# PhaetonArduinoBrd.net
KiCad netlist of a schematic drawn in EAGLE
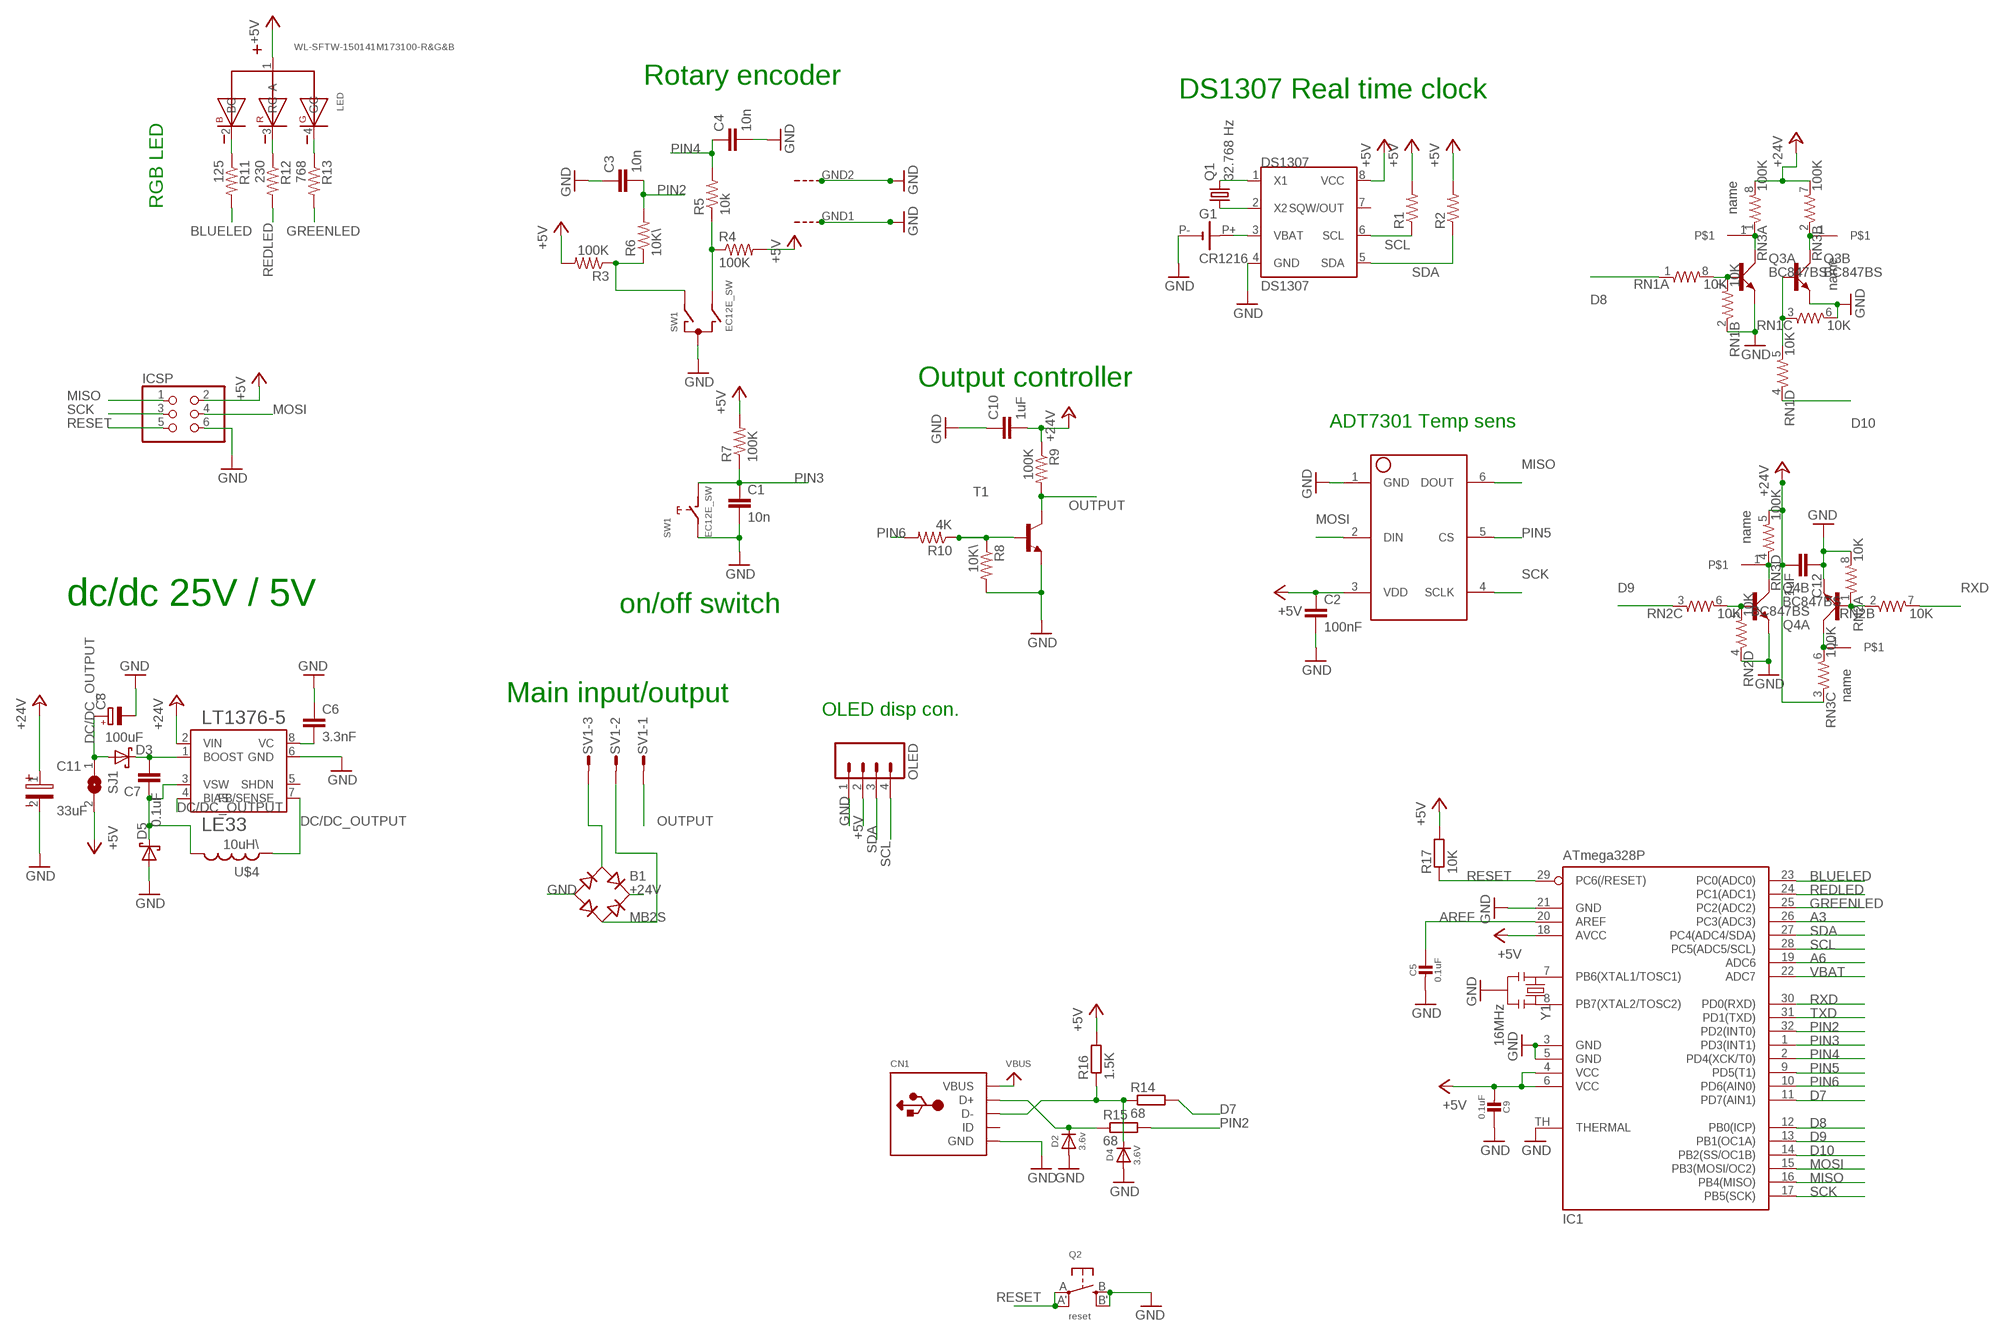
[diagram p0: schematic, sheet 1]

(export (version "E")
  (design (tool "Eeschema 10.0.6"))
  (components
    (comp (ref "ADT")
      (value "ADT7301")
      (footprint "eagle-import:SOT23-6")
      (libsource (lib "eagle-import") (part "ADT7301"))
    )
    (comp (ref "B1")
      (value "MB2S")
      (footprint "eagle-import:SOIC-4")
      (libsource (lib "eagle-import") (part "MBS2"))
    )
    (comp (ref "C1")
      (value "10n")
      (footprint "eagle-import:C0504")
      (libsource (lib "eagle-import") (part "C-EUC0504"))
    )
    (comp (ref "C2")
      (value "100nF")
      (footprint "eagle-import:C0504")
      (libsource (lib "eagle-import") (part "C-EUC0504"))
    )
    (comp (ref "C3")
      (value "10n")
      (footprint "eagle-import:C0504")
      (libsource (lib "eagle-import") (part "C-EUC0504"))
    )
    (comp (ref "C4")
      (value "10n")
      (footprint "eagle-import:C0504")
      (libsource (lib "eagle-import") (part "C-EUC0504"))
    )
    (comp (ref "C5")
      (value "0.1uF")
      (footprint "eagle-import:_0805MP")
      (libsource (lib "eagle-import") (part "CAP_CERAMIC_0805MP"))
    )
    (comp (ref "C6")
      (value "3.3nF")
      (footprint "eagle-import:C0504")
      (libsource (lib "eagle-import") (part "C-EUC0504"))
    )
    (comp (ref "C7")
      (value "0.1uF")
      (footprint "eagle-import:C0504")
      (libsource (lib "eagle-import") (part "C-EUC0504"))
    )
    (comp (ref "C8")
      (value "100uF")
      (footprint "eagle-import:CT7343")
      (libsource (lib "eagle-import") (part "CPOL-EUCT7343"))
    )
    (comp (ref "C9")
      (value "0.1uF")
      (footprint "eagle-import:_0805MP")
      (libsource (lib "eagle-import") (part "CAP_CERAMIC_0805MP"))
    )
    (comp (ref "C10")
      (value "1uF")
      (footprint "eagle-import:C0402")
      (libsource (lib "eagle-import") (part "resistor_C-EUC0402"))
    )
    (comp (ref "C11")
      (value "33uF")
      (footprint "eagle-import:3X1.6X1.4(BXCXA)")
      (libsource (lib "eagle-import") (part "WCAP-ASLI_5X5.5(DXL)"))
    )
    (comp (ref "C12")
      (value "1uF")
      (footprint "eagle-import:C0402")
      (libsource (lib "eagle-import") (part "resistor_C-EUC0402"))
    )
    (comp (ref "CN1")
      (value "USBMINIB")
      (footprint "eagle-import:USB-MINIB")
      (libsource (lib "eagle-import") (part "USBMINIB"))
    )
    (comp (ref "D2")
      (value "3.6v")
      (footprint "eagle-import:SOD-323")
      (libsource (lib "eagle-import") (part "DIODESOD-323"))
    )
    (comp (ref "D3")
      (value "SCHOTTKY")
      (footprint "eagle-import:DO214")
      (libsource (lib "eagle-import") (part "SCHOTTKY"))
    )
    (comp (ref "D4")
      (value "3.6V")
      (footprint "eagle-import:SOD-323")
      (libsource (lib "eagle-import") (part "DIODESOD-323"))
    )
    (comp (ref "D5")
      (value "SCHOTTKY")
      (footprint "eagle-import:DO214")
      (libsource (lib "eagle-import") (part "SCHOTTKY"))
    )
    (comp (ref "DS1307")
      (value "DS1307")
      (footprint "eagle-import:SOIC-8")
      (libsource (lib "eagle-import") (part "DS1307"))
    )
    (comp (ref "G1")
      (value "CR1216")
      (footprint "eagle-import:SMTU1225-LF")
      (libsource (lib "eagle-import") (part "CR1216"))
    )
    (comp (ref "IC1")
      (value "ATmega328P")
      (footprint "eagle-import:MLF32-TH")
      (fields (field (name "MPN") "ATMEGA88PA-MU"))
      (libsource (lib "eagle-import") (part "MEGA8-MI"))
    )
    (comp (ref "ICSP")
      (value "PINHD-2X3")
      (footprint "eagle-import:2X03")
      (libsource (lib "eagle-import") (part "PINHD-2X3"))
    )
    (comp (ref "LED")
      (value "WL-SFTW-150141M173100-R&G&B")
      (footprint "eagle-import:3528-COMMON-ANODE")
      (libsource (lib "eagle-import") (part "WL-SFTW-150141M173100-R&G&B"))
    )
    (comp (ref "LT1376-5")
      (value "LE33")
      (footprint "eagle-import:SO08")
      (libsource (lib "eagle-import") (part "LE33"))
    )
    (comp (ref "OLED")
      (value "M04")
      (footprint "eagle-import:04P")
      (libsource (lib "eagle-import") (part "M04"))
    )
    (comp (ref "OUTPUT2")
      (value "MINICONECTOR")
      (footprint "eagle-import:SMD")
      (libsource (lib "eagle-import") (part "MINICONECTOR"))
    )
    (comp (ref "Q1")
      (value "32.768 Hz")
      (footprint "eagle-import:TC26V")
      (libsource (lib "eagle-import") (part "CRYSTALTC26V"))
    )
    (comp (ref "Q2")
      (value "reset")
      (footprint "eagle-import:BTN_KMR2_4.6X2.8")
      (libsource (lib "eagle-import") (part "SWITCH_TACT_SMT4.6X2.8"))
    )
    (comp (ref "Q3")
      (value "BC847BS")
      (footprint "eagle-import:SOT363_PHILIPS")
      (libsource (lib "eagle-import") (part "BC847BS"))
    )
    (comp (ref "Q4")
      (value "BC847BS")
      (footprint "eagle-import:SOT363_PHILIPS")
      (libsource (lib "eagle-import") (part "BC847BS"))
    )
    (comp (ref "R1")
      (value "RESISTOR")
      (footprint "eagle-import:0805")
      (libsource (lib "eagle-import") (part "RESISTOR"))
    )
    (comp (ref "R2")
      (value "RESISTOR")
      (footprint "eagle-import:0805")
      (libsource (lib "eagle-import") (part "RESISTOR"))
    )
    (comp (ref "R3")
      (value "100K")
      (footprint "eagle-import:0805")
      (libsource (lib "eagle-import") (part "RESISTOR"))
    )
    (comp (ref "R4")
      (value "100K")
      (footprint "eagle-import:0805")
      (libsource (lib "eagle-import") (part "RESISTOR"))
    )
    (comp (ref "R5")
      (value "10k")
      (footprint "eagle-import:0805")
      (libsource (lib "eagle-import") (part "RESISTOR"))
    )
    (comp (ref "R6")
      (value "10K\\")
      (footprint "eagle-import:0805")
      (libsource (lib "eagle-import") (part "RESISTOR"))
    )
    (comp (ref "R7")
      (value "100K")
      (footprint "eagle-import:0805")
      (libsource (lib "eagle-import") (part "RESISTOR"))
    )
    (comp (ref "R8")
      (value "10K\\")
      (footprint "eagle-import:0805")
      (libsource (lib "eagle-import") (part "RESISTOR"))
    )
    (comp (ref "R9")
      (value "100K")
      (footprint "eagle-import:0805")
      (libsource (lib "eagle-import") (part "RESISTOR"))
    )
    (comp (ref "R10")
      (value "4K")
      (footprint "eagle-import:0805")
      (libsource (lib "eagle-import") (part "RESISTOR"))
    )
    (comp (ref "R11")
      (value "125")
      (footprint "eagle-import:0805")
      (libsource (lib "eagle-import") (part "RESISTOR"))
    )
    (comp (ref "R12")
      (value "230")
      (footprint "eagle-import:0805")
      (libsource (lib "eagle-import") (part "RESISTOR"))
    )
    (comp (ref "R13")
      (value "768")
      (footprint "eagle-import:0805")
      (libsource (lib "eagle-import") (part "RESISTOR"))
    )
    (comp (ref "R14")
      (value "68")
      (footprint "eagle-import:R0603")
      (libsource (lib "eagle-import") (part "R-EU_R0603"))
    )
    (comp (ref "R15")
      (value "68")
      (footprint "eagle-import:R0603")
      (libsource (lib "eagle-import") (part "R-EU_R0603"))
    )
    (comp (ref "R16")
      (value "1.5K")
      (footprint "eagle-import:R0603")
      (libsource (lib "eagle-import") (part "R-EU_R0603"))
    )
    (comp (ref "R17")
      (value "10K")
      (footprint "eagle-import:R0603")
      (libsource (lib "eagle-import") (part "R-EU_R0603"))
    )
    (comp (ref "RN1")
      (value "10K")
      (footprint "eagle-import:741-8")
      (libsource (lib "eagle-import") (part "741-8_S"))
    )
    (comp (ref "RN2")
      (value "10K")
      (footprint "eagle-import:741-8")
      (libsource (lib "eagle-import") (part "741-8_S"))
    )
    (comp (ref "RN3")
      (value "100K")
      (footprint "eagle-import:741-8")
      (libsource (lib "eagle-import") (part "741-8_S"))
    )
    (comp (ref "SJ1") (value "SJ") (footprint "eagle-import:SJ") (libsource (lib "eagle-import") (part "SJ")))
    (comp (ref "SV1")
      (value "MT6-3")
      (footprint "eagle-import:MT6-3")
      (libsource (lib "eagle-import") (part "MT6-3"))
    )
    (comp (ref "SW1")
      (value "EC12E_SW")
      (footprint "eagle-import:ALPS_EC12E_SW")
      (fields (field (name "MPN") "EC12E2424407"))
      (libsource (lib "eagle-import") (part "EC12E_SW"))
    )
    (comp (ref "T1")
      (value "BC818-16-NPN-SOT23-BEC")
      (footprint "eagle-import:SOT23-BEC")
      (libsource (lib "eagle-import") (part "-NPN-SOT23-BECBC818-16"))
    )
    (comp (ref "U$3")
      (value "MINICONECTOR")
      (footprint "eagle-import:SMD")
      (libsource (lib "eagle-import") (part "MINICONECTOR"))
    )
    (comp (ref "U$4")
      (value "10uH\\")
      (footprint "eagle-import:103MRB")
      (libsource (lib "eagle-import") (part "LPS3314-103MRB"))
    )
    (comp (ref "U$5")
      (value "MINICONECTOR")
      (footprint "eagle-import:SMD")
      (libsource (lib "eagle-import") (part "MINICONECTOR"))
    )
    (comp (ref "U$6")
      (value "MINICONECTOR")
      (footprint "eagle-import:SMD")
      (libsource (lib "eagle-import") (part "MINICONECTOR"))
    )
    (comp (ref "Y1")
      (value "16MHz")
      (footprint "eagle-import:RESONATOR-SMD")
      (libsource (lib "eagle-import") (part "RESONATORSMD"))
    )
  )
  (nets
    (net (code "1") (name "+5V") (class "Default")
      (node (ref "ADT") (pin "3") (pinfunction "VDD_3") (pintype "bidirectional"))
      (node (ref "C2") (pin "1") (pinfunction "1_1") (pintype "passive"))
      (node (ref "C9") (pin "2") (pinfunction "2_2") (pintype "passive"))
      (node (ref "DS1307") (pin "8") (pinfunction "VCC_8") (pintype "power_in"))
      (node (ref "IC1") (pin "18") (pinfunction "AVCC_18") (pintype "power_in"))
      (node (ref "IC1") (pin "4") (pinfunction "VCC_4") (pintype "power_in"))
      (node (ref "IC1") (pin "6") (pinfunction "VCC_6") (pintype "power_in"))
      (node (ref "ICSP") (pin "2") (pinfunction "2_2") (pintype "passive"))
      (node (ref "LED") (pin "1") (pinfunction "A_1") (pintype "bidirectional"))
      (node (ref "OLED") (pin "2") (pinfunction "2_2") (pintype "passive"))
      (node (ref "R1") (pin "2") (pinfunction "2_2") (pintype "passive"))
      (node (ref "R16") (pin "2") (pinfunction "2_2") (pintype "passive"))
      (node (ref "R17") (pin "2") (pinfunction "2_2") (pintype "passive"))
      (node (ref "R2") (pin "2") (pinfunction "2_2") (pintype "passive"))
      (node (ref "R3") (pin "2") (pinfunction "2_2") (pintype "passive"))
      (node (ref "R4") (pin "2") (pinfunction "2_2") (pintype "passive"))
      (node (ref "R7") (pin "2") (pinfunction "2_2") (pintype "passive"))
      (node (ref "SJ1") (pin "2") (pinfunction "2_2") (pintype "passive"))
    )
    (net (code "2") (name "+24V") (class "Default")
      (node (ref "B1") (pin "+") (pinfunction "+_+") (pintype "passive"))
      (node (ref "C10") (pin "2") (pinfunction "2_2") (pintype "passive"))
      (node (ref "C11") (pin "1") (pinfunction "1_1") (pintype "bidirectional"))
      (node (ref "C12") (pin "2") (pinfunction "2_2") (pintype "passive"))
      (node (ref "LT1376-5") (pin "2") (pinfunction "VIN_2") (pintype "input"))
      (node (ref "R9") (pin "1") (pinfunction "1_1") (pintype "passive"))
      (node (ref "RN3") (pin "3") (pinfunction "1_3") (pintype "passive"))
      (node (ref "RN3") (pin "5") (pinfunction "2_5") (pintype "passive"))
      (node (ref "RN3") (pin "7") (pinfunction "2_7") (pintype "passive"))
      (node (ref "RN3") (pin "8") (pinfunction "2_8") (pintype "passive"))
    )
    (net (code "3") (name "/A3") (class "Default")
      (node (ref "IC1") (pin "26") (pinfunction "PC3(ADC3)_26") (pintype "bidirectional"))
    )
    (net (code "4") (name "/A6") (class "Default")
      (node (ref "IC1") (pin "19") (pinfunction "ADC6_19") (pintype "bidirectional"))
    )
    (net (code "5") (name "/AREF") (class "Default")
      (node (ref "C5") (pin "1") (pinfunction "1_1") (pintype "passive"))
      (node (ref "IC1") (pin "20") (pinfunction "AREF_20") (pintype "passive"))
    )
    (net (code "6") (name "/BLUELED") (class "Default")
      (node (ref "IC1") (pin "23") (pinfunction "PC0(ADC0)_23") (pintype "bidirectional"))
      (node (ref "R11") (pin "2") (pinfunction "2_2") (pintype "passive"))
    )
    (net (code "7") (name "/D7") (class "Default")
      (node (ref "IC1") (pin "11") (pinfunction "PD7(AIN1)_11") (pintype "bidirectional"))
      (node (ref "R14") (pin "2") (pinfunction "2_2") (pintype "passive"))
    )
    (net (code "8") (name "/D8") (class "Default")
      (node (ref "IC1") (pin "12") (pinfunction "PB0(ICP)_12") (pintype "bidirectional"))
      (node (ref "RN1") (pin "1") (pinfunction "1_1") (pintype "passive"))
    )
    (net (code "9") (name "/D9") (class "Default")
      (node (ref "IC1") (pin "13") (pinfunction "PB1(OC1A)_13") (pintype "bidirectional"))
      (node (ref "RN2") (pin "3") (pinfunction "1_3") (pintype "passive"))
    )
    (net (code "10") (name "/D10") (class "Default")
      (node (ref "IC1") (pin "14") (pinfunction "PB2(SS/OC1B)_14") (pintype "bidirectional"))
      (node (ref "RN1") (pin "4") (pinfunction "1_4") (pintype "passive"))
    )
    (net (code "11") (name "/DC{slash}DC_OUTPUT") (class "Default")
      (node (ref "C8") (pin "+") (pinfunction "+_+") (pintype "passive"))
      (node (ref "D3") (pin "A") (pinfunction "A_A") (pintype "passive"))
      (node (ref "LT1376-5") (pin "4") (pinfunction "BIAS_4") (pintype "power_in"))
      (node (ref "LT1376-5") (pin "7") (pinfunction "FB/SENSE_7") (pintype "bidirectional"))
      (node (ref "SJ1") (pin "1") (pinfunction "1_1") (pintype "passive"))
      (node (ref "U$4") (pin "2") (pinfunction "P$2_2") (pintype "passive"))
    )
    (net (code "12") (name "/GREENLED") (class "Default")
      (node (ref "IC1") (pin "25") (pinfunction "PC2(ADC2)_25") (pintype "bidirectional"))
      (node (ref "R13") (pin "2") (pinfunction "2_2") (pintype "passive"))
    )
    (net (code "13") (name "/MISO") (class "Default")
      (node (ref "ADT") (pin "6") (pinfunction "DOUT_6") (pintype "bidirectional"))
      (node (ref "IC1") (pin "16") (pinfunction "PB4(MISO)_16") (pintype "bidirectional"))
      (node (ref "ICSP") (pin "1") (pinfunction "1_1") (pintype "passive"))
    )
    (net (code "14") (name "/MOSI") (class "Default")
      (node (ref "ADT") (pin "2") (pinfunction "DIN_2") (pintype "bidirectional"))
      (node (ref "IC1") (pin "15") (pinfunction "PB3(MOSI/OC2)_15") (pintype "bidirectional"))
      (node (ref "ICSP") (pin "4") (pinfunction "4_4") (pintype "passive"))
    )
    (net (code "15") (name "/OUTPUT") (class "Default")
      (node (ref "R9") (pin "2") (pinfunction "2_2") (pintype "passive"))
      (node (ref "SV1") (pin "1") (pinfunction "S_1") (pintype "passive"))
      (node (ref "T1") (pin "C") (pinfunction "C_C") (pintype "passive"))
    )
    (net (code "16") (name "/PIN2") (class "Default")
      (node (ref "C3") (pin "2") (pinfunction "2_2") (pintype "passive"))
      (node (ref "IC1") (pin "32") (pinfunction "PD2(INT0)_32") (pintype "bidirectional"))
      (node (ref "R15") (pin "2") (pinfunction "2_2") (pintype "passive"))
      (node (ref "R6") (pin "2") (pinfunction "2_2") (pintype "passive"))
    )
    (net (code "17") (name "/PIN3") (class "Default")
      (node (ref "C1") (pin "1") (pinfunction "1_1") (pintype "passive"))
      (node (ref "IC1") (pin "1") (pinfunction "PD3(INT1)_1") (pintype "bidirectional"))
      (node (ref "R7") (pin "1") (pinfunction "1_1") (pintype "passive"))
      (node (ref "SW1") (pin "D") (pinfunction "1_D") (pintype "passive"))
    )
    (net (code "18") (name "/PIN4") (class "Default")
      (node (ref "C4") (pin "1") (pinfunction "1_1") (pintype "passive"))
      (node (ref "IC1") (pin "2") (pinfunction "PD4(XCK/T0)_2") (pintype "bidirectional"))
      (node (ref "R5") (pin "2") (pinfunction "2_2") (pintype "passive"))
    )
    (net (code "19") (name "/PIN5") (class "Default")
      (node (ref "ADT") (pin "5") (pinfunction "CS_5") (pintype "bidirectional"))
      (node (ref "IC1") (pin "9") (pinfunction "PD5(T1)_9") (pintype "bidirectional"))
    )
    (net (code "20") (name "/PIN6") (class "Default")
      (node (ref "IC1") (pin "10") (pinfunction "PD6(AIN0)_10") (pintype "bidirectional"))
      (node (ref "R10") (pin "2") (pinfunction "2_2") (pintype "passive"))
    )
    (net (code "21") (name "/REDLED") (class "Default")
      (node (ref "IC1") (pin "24") (pinfunction "PC1(ADC1)_24") (pintype "bidirectional"))
      (node (ref "R12") (pin "2") (pinfunction "2_2") (pintype "passive"))
    )
    (net (code "22") (name "/RESET") (class "Default")
      (node (ref "IC1") (pin "29") (pinfunction "PC6(/RESET)_29") (pintype "bidirectional"))
      (node (ref "ICSP") (pin "5") (pinfunction "5_5") (pintype "passive"))
      (node (ref "Q2") (pin "A") (pinfunction "P_A") (pintype "passive"))
      (node (ref "Q2") (pin "A'") (pinfunction "P1_A'") (pintype "passive"))
      (node (ref "R17") (pin "1") (pinfunction "1_1") (pintype "passive"))
    )
    (net (code "23") (name "/RXD") (class "Default")
      (node (ref "IC1") (pin "30") (pinfunction "PD0(RXD)_30") (pintype "bidirectional"))
      (node (ref "RN2") (pin "7") (pinfunction "2_7") (pintype "passive"))
    )
    (net (code "24") (name "/SCK") (class "Default")
      (node (ref "ADT") (pin "4") (pinfunction "SCLK_4") (pintype "bidirectional"))
      (node (ref "IC1") (pin "17") (pinfunction "PB5(SCK)_17") (pintype "bidirectional"))
      (node (ref "ICSP") (pin "3") (pinfunction "3_3") (pintype "passive"))
    )
    (net (code "25") (name "/SCL") (class "Default")
      (node (ref "DS1307") (pin "6") (pinfunction "SCL_6") (pintype "input"))
      (node (ref "IC1") (pin "28") (pinfunction "PC5(ADC5/SCL)_28") (pintype "bidirectional"))
      (node (ref "OLED") (pin "4") (pinfunction "4_4") (pintype "passive"))
      (node (ref "R1") (pin "1") (pinfunction "1_1") (pintype "passive"))
    )
    (net (code "26") (name "/SDA") (class "Default")
      (node (ref "DS1307") (pin "5") (pinfunction "SDA_5") (pintype "bidirectional"))
      (node (ref "IC1") (pin "27") (pinfunction "PC4(ADC4/SDA)_27") (pintype "bidirectional"))
      (node (ref "OLED") (pin "3") (pinfunction "3_3") (pintype "passive"))
      (node (ref "R2") (pin "1") (pinfunction "1_1") (pintype "passive"))
    )
    (net (code "27") (name "/SHDN") (class "Default")
      (node (ref "LT1376-5") (pin "5") (pinfunction "SHDN_5") (pintype "power_in"))
    )
    (net (code "28") (name "/TXD") (class "Default")
      (node (ref "IC1") (pin "31") (pinfunction "PD1(TXD)_31") (pintype "bidirectional"))
    )
    (net (code "29") (name "/VBAT") (class "Default")
      (node (ref "DS1307") (pin "3") (pinfunction "VBAT_3") (pintype "power_in"))
      (node (ref "G1") (pin "P+") (pinfunction "+_P+") (pintype "passive"))
      (node (ref "IC1") (pin "22") (pinfunction "ADC7_22") (pintype "bidirectional"))
    )
    (net (code "30") (name "GND") (class "Default")
      (node (ref "ADT") (pin "1") (pinfunction "GND_1") (pintype "bidirectional"))
      (node (ref "B1") (pin "-") (pinfunction "-_-") (pintype "passive"))
      (node (ref "C1") (pin "2") (pinfunction "2_2") (pintype "passive"))
      (node (ref "C10") (pin "1") (pinfunction "1_1") (pintype "passive"))
      (node (ref "C11") (pin "2") (pinfunction "2_2") (pintype "bidirectional"))
      (node (ref "C12") (pin "1") (pinfunction "1_1") (pintype "passive"))
      (node (ref "C2") (pin "2") (pinfunction "2_2") (pintype "passive"))
      (node (ref "C3") (pin "1") (pinfunction "1_1") (pintype "passive"))
      (node (ref "C4") (pin "2") (pinfunction "2_2") (pintype "passive"))
      (node (ref "C5") (pin "2") (pinfunction "2_2") (pintype "passive"))
      (node (ref "C6") (pin "1") (pinfunction "1_1") (pintype "passive"))
      (node (ref "C8") (pin "-") (pinfunction "-_-") (pintype "passive"))
      (node (ref "C9") (pin "1") (pinfunction "1_1") (pintype "passive"))
      (node (ref "CN1") (pin "GND") (pinfunction "GND_GND") (pintype "power_in"))
      (node (ref "D2") (pin "A") (pinfunction "A_A") (pintype "passive"))
      (node (ref "D4") (pin "A") (pinfunction "A_A") (pintype "passive"))
      (node (ref "D5") (pin "A") (pinfunction "A_A") (pintype "passive"))
      (node (ref "DS1307") (pin "4") (pinfunction "GND_4") (pintype "power_in"))
      (node (ref "G1") (pin "P-") (pinfunction "-_P-") (pintype "passive"))
      (node (ref "IC1") (pin "21") (pinfunction "GND_21") (pintype "power_in"))
      (node (ref "IC1") (pin "3") (pinfunction "GND_3") (pintype "power_in"))
      (node (ref "IC1") (pin "5") (pinfunction "GND_5") (pintype "power_in"))
      (node (ref "IC1") (pin "TH") (pinfunction "THERMAL_TH") (pintype "passive"))
      (node (ref "ICSP") (pin "6") (pinfunction "6_6") (pintype "passive"))
      (node (ref "LT1376-5") (pin "6") (pinfunction "GND_6") (pintype "power_in"))
      (node (ref "OLED") (pin "1") (pinfunction "1_1") (pintype "passive"))
      (node (ref "Q2") (pin "B") (pinfunction "S_B") (pintype "passive"))
      (node (ref "Q2") (pin "B'") (pinfunction "S1_B'") (pintype "passive"))
      (node (ref "Q3") (pin "1") (pinfunction "E_1") (pintype "passive"))
      (node (ref "Q3") (pin "4") (pinfunction "E_4") (pintype "passive"))
      (node (ref "Q4") (pin "1") (pinfunction "E_1") (pintype "passive"))
      (node (ref "Q4") (pin "4") (pinfunction "E_4") (pintype "passive"))
      (node (ref "R8") (pin "2") (pinfunction "2_2") (pintype "passive"))
      (node (ref "RN1") (pin "2") (pinfunction "1_2") (pintype "passive"))
      (node (ref "RN1") (pin "6") (pinfunction "2_6") (pintype "passive"))
      (node (ref "RN2") (pin "4") (pinfunction "1_4") (pintype "passive"))
      (node (ref "RN2") (pin "8") (pinfunction "2_8") (pintype "passive"))
      (node (ref "SW1") (pin "C") (pinfunction "C_C") (pintype "passive"))
      (node (ref "SW1") (pin "E") (pinfunction "2_E") (pintype "passive"))
      (node (ref "SW1") (pin "GND1") (pinfunction "G_GND1") (pintype "passive"))
      (node (ref "SW1") (pin "GND2") (pinfunction "G_GND2") (pintype "passive"))
      (node (ref "T1") (pin "E") (pinfunction "E_E") (pintype "passive"))
      (node (ref "Y1") (pin "2") (pinfunction "2_2") (pintype "passive"))
    )
    (net (code "31") (name "Net-(B1-AC1)") (class "Default")
      (node (ref "B1") (pin "~1") (pinfunction "AC1_~1") (pintype "passive"))
      (node (ref "SV1") (pin "3") (pinfunction "S_3") (pintype "passive"))
    )
    (net (code "32") (name "Net-(B1-AC2)") (class "Default")
      (node (ref "B1") (pin "~2") (pinfunction "AC2_~2") (pintype "passive"))
      (node (ref "SV1") (pin "2") (pinfunction "S_2") (pintype "passive"))
    )
    (net (code "33") (name "Net-(CN1-PadD+)") (class "Default")
      (node (ref "CN1") (pin "D+") (pinfunction "D+_D+") (pintype "bidirectional"))
      (node (ref "D2") (pin "C") (pinfunction "C_C") (pintype "passive"))
      (node (ref "R15") (pin "1") (pinfunction "1_1") (pintype "passive"))
    )
    (net (code "34") (name "Net-(CN1-PadD-)") (class "Default")
      (node (ref "CN1") (pin "D-") (pinfunction "D-_D-") (pintype "bidirectional"))
      (node (ref "D4") (pin "C") (pinfunction "C_C") (pintype "passive"))
      (node (ref "R14") (pin "1") (pinfunction "1_1") (pintype "passive"))
      (node (ref "R16") (pin "1") (pinfunction "1_1") (pintype "passive"))
    )
    (net (code "35") (name "Net-(DS1307-X1)") (class "Default")
      (node (ref "DS1307") (pin "1") (pinfunction "X1_1") (pintype "input"))
      (node (ref "Q1") (pin "2") (pinfunction "2_2") (pintype "passive"))
    )
    (net (code "36") (name "Net-(DS1307-X2)") (class "Default")
      (node (ref "DS1307") (pin "2") (pinfunction "X2_2") (pintype "output"))
      (node (ref "Q1") (pin "1") (pinfunction "1_1") (pintype "passive"))
    )
    (net (code "37") (name "Net-(IC1-PB6(XTAL1{slash}TOSC1))") (class "Default")
      (node (ref "IC1") (pin "7") (pinfunction "PB6(XTAL1/TOSC1)_7") (pintype "bidirectional"))
      (node (ref "Y1") (pin "1") (pinfunction "1_1") (pintype "passive"))
    )
    (net (code "38") (name "Net-(IC1-PB7(XTAL2{slash}TOSC2))") (class "Default")
      (node (ref "IC1") (pin "8") (pinfunction "PB7(XTAL2/TOSC2)_8") (pintype "bidirectional"))
      (node (ref "Y1") (pin "3") (pinfunction "3_3") (pintype "passive"))
    )
    (net (code "39") (name "Net-(LED-BC)") (class "Default")
      (node (ref "LED") (pin "2") (pinfunction "BC_2") (pintype "bidirectional"))
      (node (ref "R11") (pin "1") (pinfunction "1_1") (pintype "passive"))
    )
    (net (code "40") (name "Net-(LED-GC)") (class "Default")
      (node (ref "LED") (pin "4") (pinfunction "GC_4") (pintype "bidirectional"))
      (node (ref "R13") (pin "1") (pinfunction "1_1") (pintype "passive"))
    )
    (net (code "41") (name "Net-(LED-RC)") (class "Default")
      (node (ref "LED") (pin "3") (pinfunction "RC_3") (pintype "bidirectional"))
      (node (ref "R12") (pin "1") (pinfunction "1_1") (pintype "passive"))
    )
    (net (code "42") (name "Net-(LT1376-5-BOOST)") (class "Default")
      (node (ref "C7") (pin "2") (pinfunction "2_2") (pintype "passive"))
      (node (ref "D3") (pin "C") (pinfunction "C_C") (pintype "passive"))
      (node (ref "LT1376-5") (pin "1") (pinfunction "BOOST_1") (pintype "input"))
    )
    (net (code "43") (name "Net-(LT1376-5-VC)") (class "Default")
      (node (ref "C6") (pin "2") (pinfunction "2_2") (pintype "passive"))
      (node (ref "LT1376-5") (pin "8") (pinfunction "VC_8") (pintype "output"))
    )
    (net (code "44") (name "Net-(LT1376-5-VSW)") (class "Default")
      (node (ref "C7") (pin "1") (pinfunction "1_1") (pintype "passive"))
      (node (ref "D5") (pin "C") (pinfunction "C_C") (pintype "passive"))
      (node (ref "LT1376-5") (pin "3") (pinfunction "VSW_3") (pintype "power_in"))
      (node (ref "U$4") (pin "1") (pinfunction "P$1_1") (pintype "passive"))
    )
    (net (code "45") (name "Net-(OUTPUT2-P$1)") (class "Default")
      (node (ref "OUTPUT2") (pin "1") (pinfunction "P$1_1") (pintype "bidirectional"))
      (node (ref "Q3") (pin "6") (pinfunction "C_6") (pintype "passive"))
      (node (ref "RN3") (pin "1") (pinfunction "1_1") (pintype "passive"))
    )
    (net (code "46") (name "Net-(Q3A-B)") (class "Default")
      (node (ref "Q3") (pin "2") (pinfunction "B_2") (pintype "passive"))
      (node (ref "RN1") (pin "7") (pinfunction "2_7") (pintype "passive"))
      (node (ref "RN1") (pin "8") (pinfunction "2_8") (pintype "passive"))
    )
    (net (code "47") (name "Net-(Q3B-B)") (class "Default")
      (node (ref "Q3") (pin "5") (pinfunction "B_5") (pintype "passive"))
      (node (ref "RN1") (pin "3") (pinfunction "1_3") (pintype "passive"))
      (node (ref "RN1") (pin "5") (pinfunction "2_5") (pintype "passive"))
    )
    (net (code "48") (name "Net-(Q3B-C)") (class "Default")
      (node (ref "Q3") (pin "3") (pinfunction "C_3") (pintype "passive"))
      (node (ref "RN3") (pin "2") (pinfunction "1_2") (pintype "passive"))
      (node (ref "U$3") (pin "1") (pinfunction "P$1_1") (pintype "bidirectional"))
    )
    (net (code "49") (name "Net-(Q4A-B)") (class "Default")
      (node (ref "Q4") (pin "2") (pinfunction "B_2") (pintype "passive"))
      (node (ref "RN2") (pin "1") (pinfunction "1_1") (pintype "passive"))
      (node (ref "RN2") (pin "2") (pinfunction "1_2") (pintype "passive"))
    )
    (net (code "50") (name "Net-(Q4A-C)") (class "Default")
      (node (ref "Q4") (pin "6") (pinfunction "C_6") (pintype "passive"))
      (node (ref "RN3") (pin "6") (pinfunction "2_6") (pintype "passive"))
      (node (ref "U$5") (pin "1") (pinfunction "P$1_1") (pintype "bidirectional"))
    )
    (net (code "51") (name "Net-(Q4B-B)") (class "Default")
      (node (ref "Q4") (pin "5") (pinfunction "B_5") (pintype "passive"))
      (node (ref "RN2") (pin "5") (pinfunction "2_5") (pintype "passive"))
      (node (ref "RN2") (pin "6") (pinfunction "2_6") (pintype "passive"))
    )
    (net (code "52") (name "Net-(Q4B-C)") (class "Default")
      (node (ref "Q4") (pin "3") (pinfunction "C_3") (pintype "passive"))
      (node (ref "RN3") (pin "4") (pinfunction "1_4") (pintype "passive"))
      (node (ref "U$6") (pin "1") (pinfunction "P$1_1") (pintype "bidirectional"))
    )
    (net (code "53") (name "Net-(R3-Pad1)") (class "Default")
      (node (ref "R3") (pin "1") (pinfunction "1_1") (pintype "passive"))
      (node (ref "R6") (pin "1") (pinfunction "1_1") (pintype "passive"))
      (node (ref "SW1") (pin "A") (pinfunction "A_A") (pintype "passive"))
    )
    (net (code "54") (name "Net-(R4-Pad1)") (class "Default")
      (node (ref "R4") (pin "1") (pinfunction "1_1") (pintype "passive"))
      (node (ref "R5") (pin "1") (pinfunction "1_1") (pintype "passive"))
      (node (ref "SW1") (pin "B") (pinfunction "B_B") (pintype "passive"))
    )
    (net (code "55") (name "Net-(R10-Pad1)") (class "Default")
      (node (ref "R10") (pin "1") (pinfunction "1_1") (pintype "passive"))
      (node (ref "R8") (pin "1") (pinfunction "1_1") (pintype "passive"))
      (node (ref "T1") (pin "B") (pinfunction "B_B") (pintype "passive"))
    )
    (net (code "56") (name "VBUS") (class "Default")
      (node (ref "CN1") (pin "VBUS") (pinfunction "VBUS_VBUS") (pintype "power_in"))
    )
    (net (code "57") (name "unconnected-(CN1-PadID)") (class "Default")
      (node (ref "CN1") (pin "ID") (pinfunction "ID_ID") (pintype "bidirectional"))
    )
    (net (code "58") (name "unconnected-(DS1307-SQW{slash}OUT-Pad7)") (class "Default")
      (node (ref "DS1307") (pin "7") (pinfunction "SQW/OUT_7") (pintype "output"))
    )
  )
)
